# Alchemist.net
KiCad netlist of a schematic drawn in EAGLE
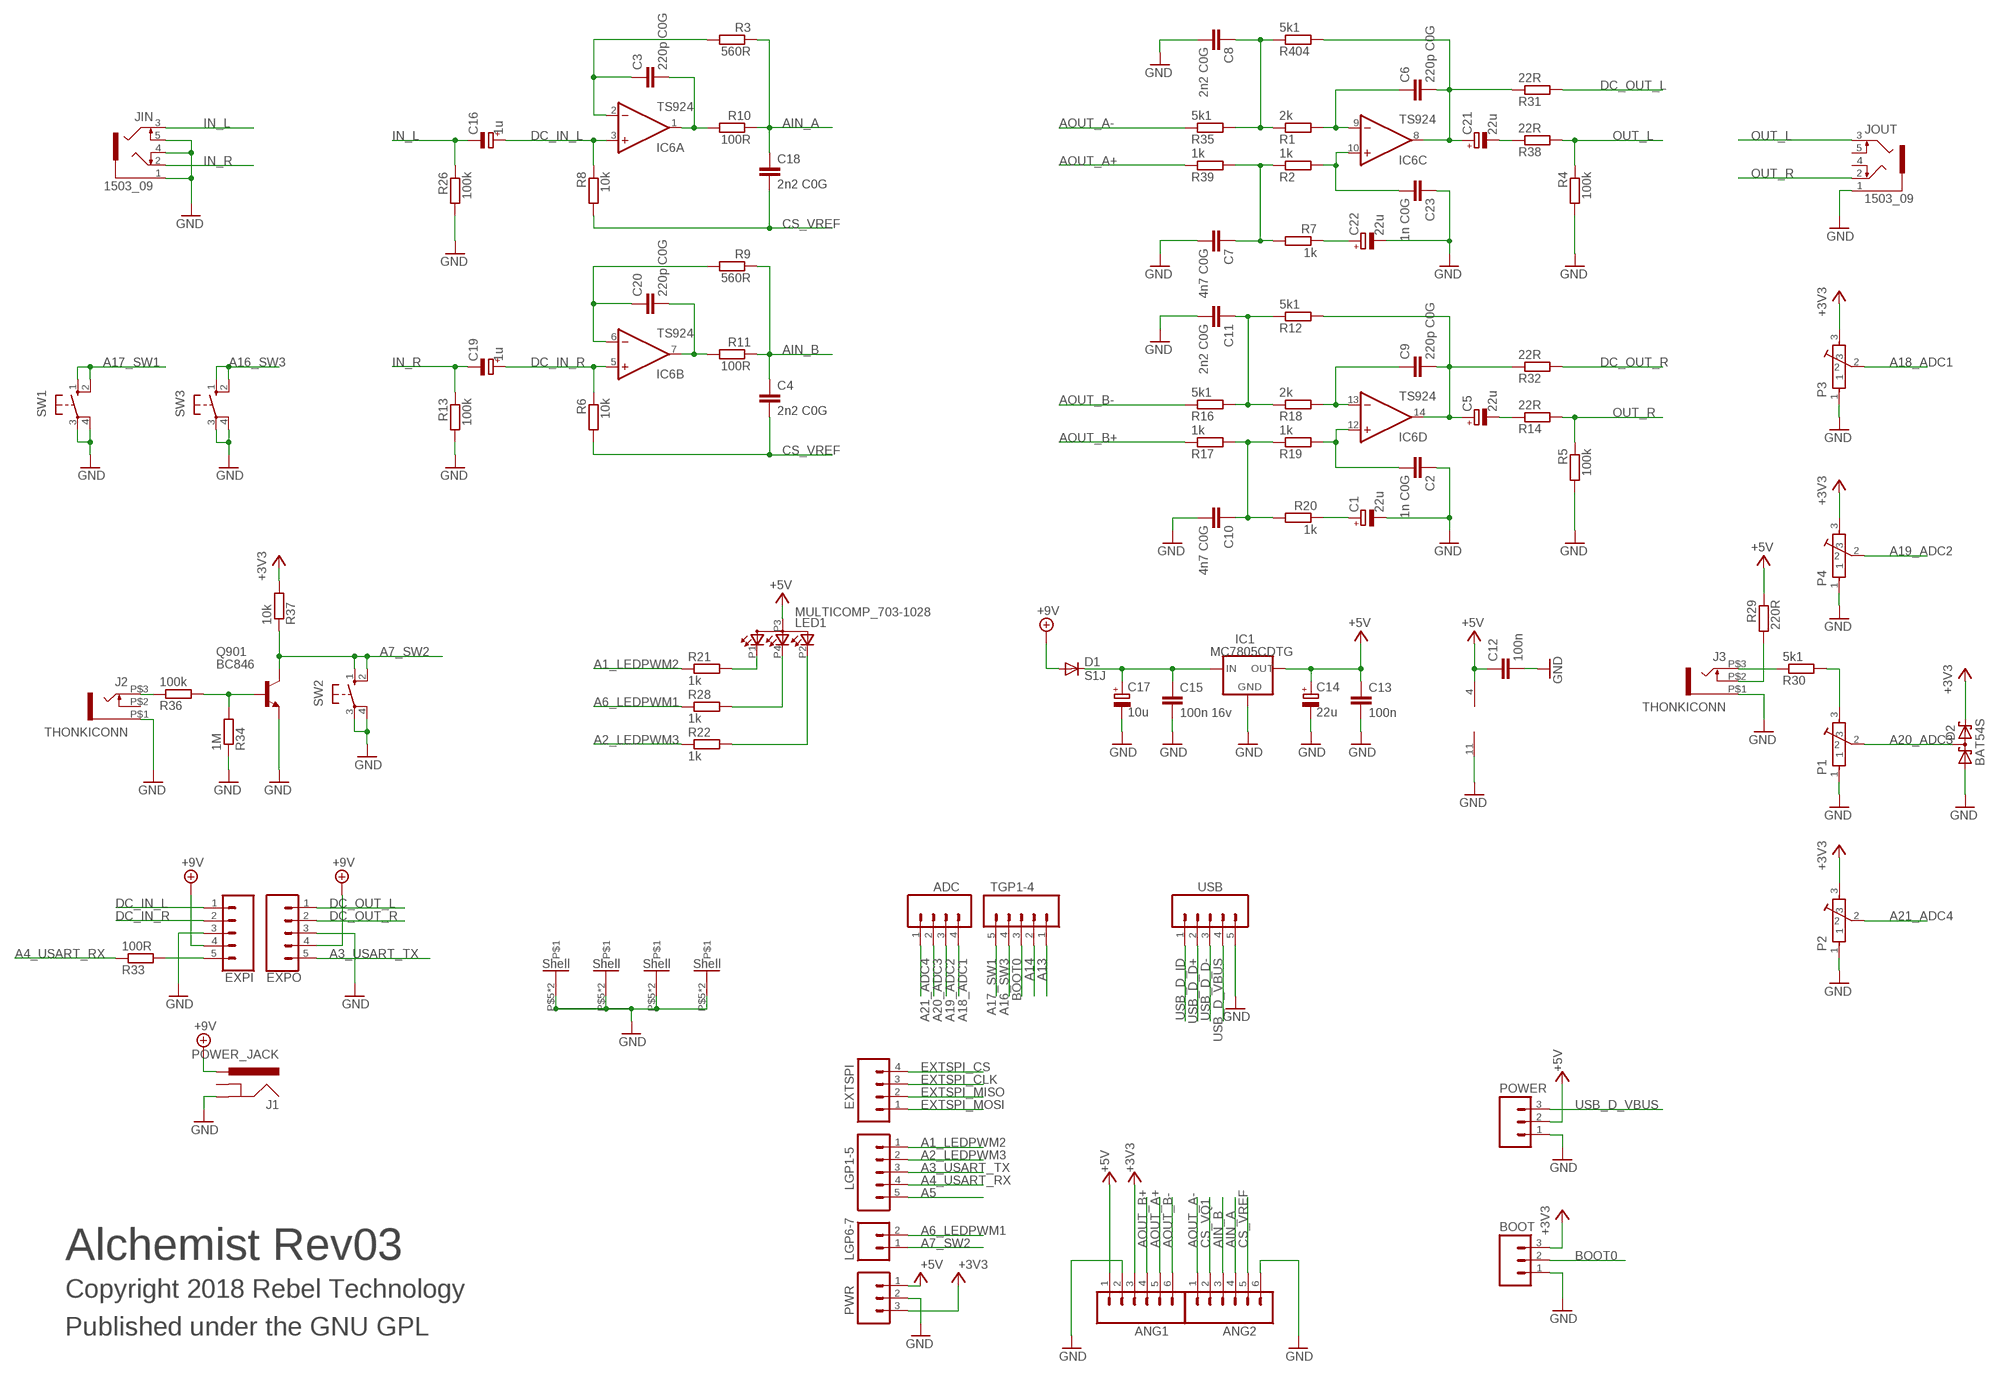
[diagram p0: schematic, sheet 1]

(export (version "E")
  (design (tool "Eeschema 10.0.6"))
  (components
    (comp (ref "ADC")
      (value "M04PTH")
      (footprint "eagle-import:1X04")
      (libsource (lib "eagle-import") (part "M04PTH"))
    )
    (comp (ref "ANG1")
      (value "M06SIP")
      (footprint "eagle-import:1X06")
      (libsource (lib "eagle-import") (part "M06SIP"))
    )
    (comp (ref "ANG2")
      (value "M06SIP")
      (footprint "eagle-import:1X06")
      (libsource (lib "eagle-import") (part "M06SIP"))
    )
    (comp (ref "BOOT")
      (value "M03PTH")
      (footprint "eagle-import:1X03")
      (libsource (lib "eagle-import") (part "M03PTH"))
    )
    (comp (ref "C1")
      (value "22u")
      (footprint "eagle-import:CPOL-5")
      (libsource (lib "eagle-import") (part "CPOL-EU153CLV-0505"))
    )
    (comp (ref "C2")
      (value "1n C0G")
      (footprint "eagle-import:C0603")
      (libsource (lib "eagle-import") (part "resistor_C-EUC0603"))
    )
    (comp (ref "C3")
      (value "220p C0G")
      (footprint "eagle-import:C0603")
      (libsource (lib "eagle-import") (part "resistor_C-EUC0603"))
    )
    (comp (ref "C4")
      (value "2n2 C0G")
      (footprint "eagle-import:C0603")
      (libsource (lib "eagle-import") (part "resistor_C-EUC0603"))
    )
    (comp (ref "C5")
      (value "22u")
      (footprint "eagle-import:CPOL-5")
      (libsource (lib "eagle-import") (part "CPOL-EU153CLV-0505"))
    )
    (comp (ref "C6")
      (value "220p C0G")
      (footprint "eagle-import:C0603")
      (libsource (lib "eagle-import") (part "resistor_C-EUC0603"))
    )
    (comp (ref "C7")
      (value "4n7 C0G")
      (footprint "eagle-import:C0603")
      (libsource (lib "eagle-import") (part "resistor_C-EUC0603"))
    )
    (comp (ref "C8")
      (value "2n2 C0G")
      (footprint "eagle-import:C0603")
      (libsource (lib "eagle-import") (part "resistor_C-EUC0603"))
    )
    (comp (ref "C9")
      (value "220p C0G")
      (footprint "eagle-import:C0603")
      (libsource (lib "eagle-import") (part "resistor_C-EUC0603"))
    )
    (comp (ref "C10")
      (value "4n7 C0G")
      (footprint "eagle-import:C0603")
      (libsource (lib "eagle-import") (part "resistor_C-EUC0603"))
    )
    (comp (ref "C11")
      (value "2n2 C0G")
      (footprint "eagle-import:C0603")
      (libsource (lib "eagle-import") (part "resistor_C-EUC0603"))
    )
    (comp (ref "C12")
      (value "100n")
      (footprint "eagle-import:C0603")
      (libsource (lib "eagle-import") (part "resistor_C-EUC0603"))
    )
    (comp (ref "C13")
      (value "100n")
      (footprint "eagle-import:C0603")
      (libsource (lib "eagle-import") (part "C-EUC0603"))
    )
    (comp (ref "C14")
      (value "22u")
      (footprint "eagle-import:CPOL-5")
      (libsource (lib "eagle-import") (part "CPOL-EU153CLV-0505"))
    )
    (comp (ref "C15")
      (value "100n 16v")
      (footprint "eagle-import:C0603")
      (libsource (lib "eagle-import") (part "C-EUC0603"))
    )
    (comp (ref "C16")
      (value "1u")
      (footprint "eagle-import:153CLV-0405")
      (libsource (lib "eagle-import") (part "CPOL-EU153CLV-0405"))
    )
    (comp (ref "C17")
      (value "10u")
      (footprint "eagle-import:153CLV-0405")
      (libsource (lib "eagle-import") (part "CPOL-EU153CLV-0405"))
    )
    (comp (ref "C18")
      (value "2n2 C0G")
      (footprint "eagle-import:C0603")
      (libsource (lib "eagle-import") (part "resistor_C-EUC0603"))
    )
    (comp (ref "C19")
      (value "1u")
      (footprint "eagle-import:153CLV-0405")
      (libsource (lib "eagle-import") (part "CPOL-EU153CLV-0405"))
    )
    (comp (ref "C20")
      (value "220p C0G")
      (footprint "eagle-import:C0603")
      (libsource (lib "eagle-import") (part "resistor_C-EUC0603"))
    )
    (comp (ref "C21")
      (value "22u")
      (footprint "eagle-import:CPOL-5")
      (libsource (lib "eagle-import") (part "CPOL-EU153CLV-0505"))
    )
    (comp (ref "C22")
      (value "22u")
      (footprint "eagle-import:CPOL-5")
      (libsource (lib "eagle-import") (part "CPOL-EU153CLV-0505"))
    )
    (comp (ref "C23")
      (value "1n C0G")
      (footprint "eagle-import:C0603")
      (libsource (lib "eagle-import") (part "resistor_C-EUC0603"))
    )
    (comp (ref "D1")
      (value "S1J")
      (footprint "eagle-import:SMA-DIODE")
      (libsource (lib "eagle-import") (part "DIODESMA"))
    )
    (comp (ref "D2")
      (value "BAT54S")
      (footprint "eagle-import:SOT23")
      (libsource (lib "eagle-import") (part "BAT54S"))
    )
    (comp (ref "EXPI")
      (value "CONN_05JST-VERT")
      (footprint "eagle-import:JST-5-PTH-VERT")
      (libsource (lib "eagle-import") (part "CONN_05JST-VERT"))
    )
    (comp (ref "EXPO")
      (value "CONN_05JST-VERT")
      (footprint "eagle-import:JST-5-PTH-VERT")
      (libsource (lib "eagle-import") (part "CONN_05JST-VERT"))
    )
    (comp (ref "EXTSPI")
      (value "M04PTH")
      (footprint "eagle-import:1X04")
      (libsource (lib "eagle-import") (part "M04PTH"))
    )
    (comp (ref "IC1")
      (value "MC7805CDTG")
      (footprint "eagle-import:DPACK")
      (libsource (lib "eagle-import") (part "MC78XX"))
    )
    (comp (ref "IC6")
      (value "TS924")
      (footprint "eagle-import:SO14")
      (libsource (lib "eagle-import") (part "LM324D"))
    )
    (comp (ref "J1")
      (value "POWER_JACK")
      (footprint "eagle-import:DC_JACK_SLOT")
      (libsource (lib "eagle-import") (part "POWER_JACK"))
    )
    (comp (ref "J2")
      (value "THONKICONN")
      (footprint "eagle-import:THONKICONN")
      (libsource (lib "eagle-import") (part "THONKICONN"))
    )
    (comp (ref "J3")
      (value "THONKICONN")
      (footprint "eagle-import:THONKICONN")
      (libsource (lib "eagle-import") (part "THONKICONN"))
    )
    (comp (ref "JIN")
      (value "1503_09")
      (footprint "eagle-import:1503_09")
      (libsource (lib "eagle-import") (part "1503_09"))
    )
    (comp (ref "JOUT")
      (value "1503_09")
      (footprint "eagle-import:1503_09")
      (libsource (lib "eagle-import") (part "1503_09"))
    )
    (comp (ref "LED1")
      (value "MULTICOMP_703-1028")
      (footprint "eagle-import:RGB-LED-703-1028")
      (libsource (lib "eagle-import") (part "MULTICOMP_703-1028"))
    )
    (comp (ref "LGP1-5")
      (value "M05PTH")
      (footprint "eagle-import:1X05")
      (libsource (lib "eagle-import") (part "M05PTH"))
    )
    (comp (ref "LGP6-7")
      (value "M02PTH")
      (footprint "eagle-import:1X02")
      (libsource (lib "eagle-import") (part "M02PTH"))
    )
    (comp (ref "P1")
      (value "POT-ALPS-RK09L1140")
      (footprint "eagle-import:POT-ALPS-RK09L1140")
      (libsource (lib "eagle-import") (part "POT-ALPS-RK09L1140"))
    )
    (comp (ref "P2")
      (value "POT-ALPS-RK09L1140")
      (footprint "eagle-import:POT-ALPS-RK09L1140")
      (libsource (lib "eagle-import") (part "POT-ALPS-RK09L1140"))
    )
    (comp (ref "P3")
      (value "POT-ALPS-RK09L1140")
      (footprint "eagle-import:POT-ALPS-RK09L1140")
      (libsource (lib "eagle-import") (part "POT-ALPS-RK09L1140"))
    )
    (comp (ref "P4")
      (value "POT-ALPS-RK09L1140")
      (footprint "eagle-import:POT-ALPS-RK09L1140")
      (libsource (lib "eagle-import") (part "POT-ALPS-RK09L1140"))
    )
    (comp (ref "POWER")
      (value "M03PTH")
      (footprint "eagle-import:1X03")
      (libsource (lib "eagle-import") (part "M03PTH"))
    )
    (comp (ref "PWR")
      (value "M03PTH")
      (footprint "eagle-import:1X03")
      (libsource (lib "eagle-import") (part "M03PTH"))
    )
    (comp (ref "Q901")
      (value "BC846")
      (footprint "eagle-import:SOT23")
      (libsource (lib "eagle-import") (part "BC846"))
    )
    (comp (ref "R1")
      (value "2k")
      (footprint "eagle-import:0603")
      (libsource (lib "eagle-import") (part "R-EU_0603"))
    )
    (comp (ref "R2")
      (value "1k")
      (footprint "eagle-import:0603")
      (libsource (lib "eagle-import") (part "R-EU_0603"))
    )
    (comp (ref "R3")
      (value "560R")
      (footprint "eagle-import:0603")
      (libsource (lib "eagle-import") (part "R-EU_0603"))
    )
    (comp (ref "R4")
      (value "100k")
      (footprint "eagle-import:0603")
      (libsource (lib "eagle-import") (part "R-EU_0603"))
    )
    (comp (ref "R5")
      (value "100k")
      (footprint "eagle-import:0603")
      (libsource (lib "eagle-import") (part "R-EU_0603"))
    )
    (comp (ref "R6")
      (value "10k")
      (footprint "eagle-import:0603")
      (libsource (lib "eagle-import") (part "R-EU_0603"))
    )
    (comp (ref "R7")
      (value "1k")
      (footprint "eagle-import:0603")
      (libsource (lib "eagle-import") (part "R-EU_0603"))
    )
    (comp (ref "R8")
      (value "10k")
      (footprint "eagle-import:0603")
      (libsource (lib "eagle-import") (part "R-EU_0603"))
    )
    (comp (ref "R9")
      (value "560R")
      (footprint "eagle-import:0603")
      (libsource (lib "eagle-import") (part "R-EU_0603"))
    )
    (comp (ref "R10")
      (value "100R")
      (footprint "eagle-import:0603")
      (libsource (lib "eagle-import") (part "R-EU_0603"))
    )
    (comp (ref "R11")
      (value "100R")
      (footprint "eagle-import:0603")
      (libsource (lib "eagle-import") (part "R-EU_0603"))
    )
    (comp (ref "R12")
      (value "5k1")
      (footprint "eagle-import:0603")
      (libsource (lib "eagle-import") (part "R-EU_0603"))
    )
    (comp (ref "R13")
      (value "100k")
      (footprint "eagle-import:0603")
      (libsource (lib "eagle-import") (part "R-EU_0603"))
    )
    (comp (ref "R14")
      (value "22R")
      (footprint "eagle-import:0603")
      (libsource (lib "eagle-import") (part "R-EU_0603"))
    )
    (comp (ref "R16")
      (value "5k1")
      (footprint "eagle-import:0603")
      (libsource (lib "eagle-import") (part "R-EU_0603"))
    )
    (comp (ref "R17")
      (value "1k")
      (footprint "eagle-import:0603")
      (libsource (lib "eagle-import") (part "R-EU_0603"))
    )
    (comp (ref "R18")
      (value "2k")
      (footprint "eagle-import:0603")
      (libsource (lib "eagle-import") (part "R-EU_0603"))
    )
    (comp (ref "R19")
      (value "1k")
      (footprint "eagle-import:0603")
      (libsource (lib "eagle-import") (part "R-EU_0603"))
    )
    (comp (ref "R20")
      (value "1k")
      (footprint "eagle-import:0603")
      (libsource (lib "eagle-import") (part "R-EU_0603"))
    )
    (comp (ref "R21")
      (value "1k")
      (footprint "eagle-import:0603")
      (libsource (lib "eagle-import") (part "R-EU_0603"))
    )
    (comp (ref "R22")
      (value "1k")
      (footprint "eagle-import:0603")
      (libsource (lib "eagle-import") (part "R-EU_0603"))
    )
    (comp (ref "R26")
      (value "100k")
      (footprint "eagle-import:0603")
      (libsource (lib "eagle-import") (part "R-EU_0603"))
    )
    (comp (ref "R28")
      (value "1k")
      (footprint "eagle-import:0603")
      (libsource (lib "eagle-import") (part "R-EU_0603"))
    )
    (comp (ref "R29")
      (value "220R")
      (footprint "eagle-import:0603")
      (libsource (lib "eagle-import") (part "R-EU_0603"))
    )
    (comp (ref "R30")
      (value "5k1")
      (footprint "eagle-import:0603")
      (libsource (lib "eagle-import") (part "R-EU_0603"))
    )
    (comp (ref "R31")
      (value "22R")
      (footprint "eagle-import:0603")
      (libsource (lib "eagle-import") (part "R-EU_0603"))
    )
    (comp (ref "R32")
      (value "22R")
      (footprint "eagle-import:0603")
      (libsource (lib "eagle-import") (part "R-EU_0603"))
    )
    (comp (ref "R33")
      (value "100R")
      (footprint "eagle-import:0603")
      (libsource (lib "eagle-import") (part "R-EU_0603"))
    )
    (comp (ref "R34")
      (value "1M")
      (footprint "eagle-import:0603")
      (libsource (lib "eagle-import") (part "R-EU_0603"))
    )
    (comp (ref "R35")
      (value "5k1")
      (footprint "eagle-import:0603")
      (libsource (lib "eagle-import") (part "R-EU_0603"))
    )
    (comp (ref "R36")
      (value "100k")
      (footprint "eagle-import:0603")
      (libsource (lib "eagle-import") (part "R-EU_0603"))
    )
    (comp (ref "R37")
      (value "10k")
      (footprint "eagle-import:0603")
      (libsource (lib "eagle-import") (part "R-EU_0603"))
    )
    (comp (ref "R38")
      (value "22R")
      (footprint "eagle-import:0603")
      (libsource (lib "eagle-import") (part "R-EU_0603"))
    )
    (comp (ref "R39")
      (value "1k")
      (footprint "eagle-import:0603")
      (libsource (lib "eagle-import") (part "R-EU_0603"))
    )
    (comp (ref "R404")
      (value "5k1")
      (footprint "eagle-import:0603")
      (libsource (lib "eagle-import") (part "R-EU_0603"))
    )
    (comp (ref "SW1")
      (value "10-XX")
      (footprint "eagle-import:B3F-10XX")
      (fields (field (name "MPN") "B3F-1000"))
      (libsource (lib "eagle-import") (part "10-XX"))
    )
    (comp (ref "SW2")
      (value "10-XX")
      (footprint "eagle-import:B3F-10XX")
      (fields (field (name "MPN") "B3F-1000"))
      (libsource (lib "eagle-import") (part "10-XX"))
    )
    (comp (ref "SW3")
      (value "10-XX")
      (footprint "eagle-import:B3F-10XX")
      (fields (field (name "MPN") "B3F-1000"))
      (libsource (lib "eagle-import") (part "10-XX"))
    )
    (comp (ref "TGP1-4")
      (value "M05PTH")
      (footprint "eagle-import:1X05")
      (libsource (lib "eagle-import") (part "M05PTH"))
    )
    (comp (ref "USB")
      (value "M05PTH")
      (footprint "eagle-import:1X05")
      (libsource (lib "eagle-import") (part "M05PTH"))
    )
  )
  (nets
    (net (code "1") (name "+3V3") (class "Default")
      (node (ref "ANG1") (pin "3") (pinfunction "3_3") (pintype "passive"))
      (node (ref "BOOT") (pin "3") (pinfunction "3_3") (pintype "passive"))
      (node (ref "D2") (pin "2") (pinfunction "C2_2") (pintype "passive"))
      (node (ref "P2") (pin "3") (pinfunction "3_3") (pintype "bidirectional"))
      (node (ref "P3") (pin "3") (pinfunction "3_3") (pintype "bidirectional"))
      (node (ref "P4") (pin "3") (pinfunction "3_3") (pintype "bidirectional"))
      (node (ref "PWR") (pin "3") (pinfunction "3_3") (pintype "passive"))
      (node (ref "R37") (pin "2") (pinfunction "2_2") (pintype "passive"))
    )
    (net (code "2") (name "+5V") (class "Default")
      (node (ref "ANG1") (pin "1") (pinfunction "1_1") (pintype "passive"))
      (node (ref "C12") (pin "1") (pinfunction "1_1") (pintype "passive"))
      (node (ref "C13") (pin "1") (pinfunction "1_1") (pintype "passive"))
      (node (ref "C14") (pin "+") (pinfunction "+_+") (pintype "passive"))
      (node (ref "IC1") (pin "3") (pinfunction "OUT_3") (pintype "passive"))
      (node (ref "IC6") (pin "4") (pinfunction "V+_4") (pintype "power_in"))
      (node (ref "LED1") (pin "P3") (pinfunction "A_P3") (pintype "passive"))
      (node (ref "POWER") (pin "2") (pinfunction "2_2") (pintype "passive"))
      (node (ref "PWR") (pin "1") (pinfunction "1_1") (pintype "passive"))
      (node (ref "R29") (pin "1") (pinfunction "1_1") (pintype "passive"))
    )
    (net (code "3") (name "+9V") (class "Default")
      (node (ref "D1") (pin "A") (pinfunction "A_A") (pintype "passive"))
      (node (ref "EXPI") (pin "4") (pinfunction "4_4") (pintype "passive"))
      (node (ref "EXPO") (pin "4") (pinfunction "4_4") (pintype "passive"))
      (node (ref "J1") (pin "PWR") (pinfunction "PWR_PWR") (pintype "bidirectional"))
    )
    (net (code "4") (name "/A1_LEDPWM2") (class "Default")
      (node (ref "LGP1-5") (pin "1") (pinfunction "1_1") (pintype "passive"))
      (node (ref "R21") (pin "1") (pinfunction "1_1") (pintype "passive"))
    )
    (net (code "5") (name "/A2_LEDPWM3") (class "Default")
      (node (ref "LGP1-5") (pin "2") (pinfunction "2_2") (pintype "passive"))
      (node (ref "R22") (pin "1") (pinfunction "1_1") (pintype "passive"))
    )
    (net (code "6") (name "/A3_USART_TX") (class "Default")
      (node (ref "EXPO") (pin "5") (pinfunction "5_5") (pintype "passive"))
      (node (ref "LGP1-5") (pin "3") (pinfunction "3_3") (pintype "passive"))
    )
    (net (code "7") (name "/A4_USART_RX") (class "Default")
      (node (ref "LGP1-5") (pin "4") (pinfunction "4_4") (pintype "passive"))
      (node (ref "R33") (pin "1") (pinfunction "1_1") (pintype "passive"))
    )
    (net (code "8") (name "/A5") (class "Default")
      (node (ref "LGP1-5") (pin "5") (pinfunction "5_5") (pintype "passive"))
    )
    (net (code "9") (name "/A6_LEDPWM1") (class "Default")
      (node (ref "LGP6-7") (pin "2") (pinfunction "2_2") (pintype "passive"))
      (node (ref "R28") (pin "1") (pinfunction "1_1") (pintype "passive"))
    )
    (net (code "10") (name "/A7_SW2") (class "Default")
      (node (ref "LGP6-7") (pin "1") (pinfunction "1_1") (pintype "passive"))
      (node (ref "Q901") (pin "3") (pinfunction "C_3") (pintype "passive"))
      (node (ref "R37") (pin "1") (pinfunction "1_1") (pintype "passive"))
      (node (ref "SW2") (pin "1") (pinfunction "S_1") (pintype "passive"))
      (node (ref "SW2") (pin "2") (pinfunction "S1_2") (pintype "passive"))
    )
    (net (code "11") (name "/A13") (class "Default")
      (node (ref "TGP1-4") (pin "1") (pinfunction "1_1") (pintype "passive"))
    )
    (net (code "12") (name "/A14") (class "Default")
      (node (ref "TGP1-4") (pin "2") (pinfunction "2_2") (pintype "passive"))
    )
    (net (code "13") (name "/A16_SW3") (class "Default")
      (node (ref "SW3") (pin "1") (pinfunction "S_1") (pintype "passive"))
      (node (ref "SW3") (pin "2") (pinfunction "S1_2") (pintype "passive"))
      (node (ref "TGP1-4") (pin "4") (pinfunction "4_4") (pintype "passive"))
    )
    (net (code "14") (name "/A17_SW1") (class "Default")
      (node (ref "SW1") (pin "1") (pinfunction "S_1") (pintype "passive"))
      (node (ref "SW1") (pin "2") (pinfunction "S1_2") (pintype "passive"))
      (node (ref "TGP1-4") (pin "5") (pinfunction "5_5") (pintype "passive"))
    )
    (net (code "15") (name "/A18_ADC1") (class "Default")
      (node (ref "ADC") (pin "4") (pinfunction "4_4") (pintype "passive"))
      (node (ref "P3") (pin "2") (pinfunction "2_2") (pintype "bidirectional"))
    )
    (net (code "16") (name "/A19_ADC2") (class "Default")
      (node (ref "ADC") (pin "3") (pinfunction "3_3") (pintype "passive"))
      (node (ref "P4") (pin "2") (pinfunction "2_2") (pintype "bidirectional"))
    )
    (net (code "17") (name "/A20_ADC3") (class "Default")
      (node (ref "ADC") (pin "2") (pinfunction "2_2") (pintype "passive"))
      (node (ref "D2") (pin "3") (pinfunction "C1A2_3") (pintype "passive"))
      (node (ref "P1") (pin "2") (pinfunction "2_2") (pintype "bidirectional"))
    )
    (net (code "18") (name "/A21_ADC4") (class "Default")
      (node (ref "ADC") (pin "1") (pinfunction "1_1") (pintype "passive"))
      (node (ref "P2") (pin "2") (pinfunction "2_2") (pintype "bidirectional"))
    )
    (net (code "19") (name "/AIN_A") (class "Default")
      (node (ref "ANG2") (pin "4") (pinfunction "4_4") (pintype "passive"))
      (node (ref "C18") (pin "1") (pinfunction "1_1") (pintype "passive"))
      (node (ref "R10") (pin "1") (pinfunction "1_1") (pintype "passive"))
      (node (ref "R3") (pin "1") (pinfunction "1_1") (pintype "passive"))
    )
    (net (code "20") (name "/AIN_B") (class "Default")
      (node (ref "ANG2") (pin "3") (pinfunction "3_3") (pintype "passive"))
      (node (ref "C4") (pin "1") (pinfunction "1_1") (pintype "passive"))
      (node (ref "R11") (pin "1") (pinfunction "1_1") (pintype "passive"))
      (node (ref "R9") (pin "1") (pinfunction "1_1") (pintype "passive"))
    )
    (net (code "21") (name "/AOUT_A+") (class "Default")
      (node (ref "ANG1") (pin "5") (pinfunction "5_5") (pintype "passive"))
      (node (ref "R39") (pin "1") (pinfunction "1_1") (pintype "passive"))
    )
    (net (code "22") (name "/AOUT_A-") (class "Default")
      (node (ref "ANG2") (pin "1") (pinfunction "1_1") (pintype "passive"))
      (node (ref "R35") (pin "1") (pinfunction "1_1") (pintype "passive"))
    )
    (net (code "23") (name "/AOUT_B+") (class "Default")
      (node (ref "ANG1") (pin "4") (pinfunction "4_4") (pintype "passive"))
      (node (ref "R17") (pin "1") (pinfunction "1_1") (pintype "passive"))
    )
    (net (code "24") (name "/AOUT_B-") (class "Default")
      (node (ref "ANG1") (pin "6") (pinfunction "6_6") (pintype "passive"))
      (node (ref "R16") (pin "1") (pinfunction "1_1") (pintype "passive"))
    )
    (net (code "25") (name "/BOOT0") (class "Default")
      (node (ref "BOOT") (pin "2") (pinfunction "2_2") (pintype "passive"))
      (node (ref "TGP1-4") (pin "3") (pinfunction "3_3") (pintype "passive"))
    )
    (net (code "26") (name "/CS_VQ1") (class "Default")
      (node (ref "ANG2") (pin "2") (pinfunction "2_2") (pintype "passive"))
    )
    (net (code "27") (name "/CS_VREF") (class "Default")
      (node (ref "ANG2") (pin "5") (pinfunction "5_5") (pintype "passive"))
      (node (ref "C18") (pin "2") (pinfunction "2_2") (pintype "passive"))
      (node (ref "C4") (pin "2") (pinfunction "2_2") (pintype "passive"))
      (node (ref "R6") (pin "2") (pinfunction "2_2") (pintype "passive"))
      (node (ref "R8") (pin "2") (pinfunction "2_2") (pintype "passive"))
    )
    (net (code "28") (name "/DC_IN_L") (class "Default")
      (node (ref "C16") (pin "+") (pinfunction "+_+") (pintype "passive"))
      (node (ref "EXPI") (pin "1") (pinfunction "1_1") (pintype "passive"))
      (node (ref "IC6") (pin "3") (pinfunction "+IN_3") (pintype "input"))
      (node (ref "R8") (pin "1") (pinfunction "1_1") (pintype "passive"))
    )
    (net (code "29") (name "/DC_IN_R") (class "Default")
      (node (ref "C19") (pin "+") (pinfunction "+_+") (pintype "passive"))
      (node (ref "EXPI") (pin "2") (pinfunction "2_2") (pintype "passive"))
      (node (ref "IC6") (pin "5") (pinfunction "+IN_5") (pintype "input"))
      (node (ref "R6") (pin "1") (pinfunction "1_1") (pintype "passive"))
    )
    (net (code "30") (name "/DC_OUT_L") (class "Default")
      (node (ref "EXPO") (pin "1") (pinfunction "1_1") (pintype "passive"))
      (node (ref "R31") (pin "2") (pinfunction "2_2") (pintype "passive"))
    )
    (net (code "31") (name "/DC_OUT_R") (class "Default")
      (node (ref "EXPO") (pin "2") (pinfunction "2_2") (pintype "passive"))
      (node (ref "R32") (pin "2") (pinfunction "2_2") (pintype "passive"))
    )
    (net (code "32") (name "/EXTSPI_CLK") (class "Default")
      (node (ref "EXTSPI") (pin "3") (pinfunction "3_3") (pintype "passive"))
    )
    (net (code "33") (name "/EXTSPI_CS") (class "Default")
      (node (ref "EXTSPI") (pin "4") (pinfunction "4_4") (pintype "passive"))
    )
    (net (code "34") (name "/EXTSPI_MISO") (class "Default")
      (node (ref "EXTSPI") (pin "2") (pinfunction "2_2") (pintype "passive"))
    )
    (net (code "35") (name "/EXTSPI_MOSI") (class "Default")
      (node (ref "EXTSPI") (pin "1") (pinfunction "1_1") (pintype "passive"))
    )
    (net (code "36") (name "/IN_L") (class "Default")
      (node (ref "C16") (pin "-") (pinfunction "-_-") (pintype "passive"))
      (node (ref "JIN") (pin "3") (pinfunction "3_3") (pintype "passive"))
      (node (ref "R26") (pin "1") (pinfunction "1_1") (pintype "passive"))
    )
    (net (code "37") (name "/IN_R") (class "Default")
      (node (ref "C19") (pin "-") (pinfunction "-_-") (pintype "passive"))
      (node (ref "JIN") (pin "2") (pinfunction "2_2") (pintype "passive"))
      (node (ref "R13") (pin "1") (pinfunction "1_1") (pintype "passive"))
    )
    (net (code "38") (name "/OUT_L") (class "Default")
      (node (ref "JOUT") (pin "3") (pinfunction "3_3") (pintype "passive"))
      (node (ref "R38") (pin "2") (pinfunction "2_2") (pintype "passive"))
      (node (ref "R4") (pin "1") (pinfunction "1_1") (pintype "passive"))
    )
    (net (code "39") (name "/OUT_R") (class "Default")
      (node (ref "JOUT") (pin "2") (pinfunction "2_2") (pintype "passive"))
      (node (ref "R14") (pin "2") (pinfunction "2_2") (pintype "passive"))
      (node (ref "R5") (pin "1") (pinfunction "1_1") (pintype "passive"))
    )
    (net (code "40") (name "/USB_D_D+") (class "Default")
      (node (ref "USB") (pin "2") (pinfunction "2_2") (pintype "passive"))
    )
    (net (code "41") (name "/USB_D_D-") (class "Default")
      (node (ref "USB") (pin "3") (pinfunction "3_3") (pintype "passive"))
    )
    (net (code "42") (name "/USB_D_ID") (class "Default")
      (node (ref "USB") (pin "1") (pinfunction "1_1") (pintype "passive"))
    )
    (net (code "43") (name "/USB_D_VBUS") (class "Default")
      (node (ref "POWER") (pin "3") (pinfunction "3_3") (pintype "passive"))
      (node (ref "USB") (pin "4") (pinfunction "4_4") (pintype "passive"))
    )
    (net (code "44") (name "GND") (class "Default")
      (node (ref "ANG1") (pin "2") (pinfunction "2_2") (pintype "passive"))
      (node (ref "ANG2") (pin "6") (pinfunction "6_6") (pintype "passive"))
      (node (ref "BOOT") (pin "1") (pinfunction "1_1") (pintype "passive"))
      (node (ref "C1") (pin "-") (pinfunction "-_-") (pintype "passive"))
      (node (ref "C10") (pin "2") (pinfunction "2_2") (pintype "passive"))
      (node (ref "C11") (pin "2") (pinfunction "2_2") (pintype "passive"))
      (node (ref "C12") (pin "2") (pinfunction "2_2") (pintype "passive"))
      (node (ref "C13") (pin "2") (pinfunction "2_2") (pintype "passive"))
      (node (ref "C14") (pin "-") (pinfunction "-_-") (pintype "passive"))
      (node (ref "C15") (pin "2") (pinfunction "2_2") (pintype "passive"))
      (node (ref "C17") (pin "-") (pinfunction "-_-") (pintype "passive"))
      (node (ref "C2") (pin "1") (pinfunction "1_1") (pintype "passive"))
      (node (ref "C22") (pin "-") (pinfunction "-_-") (pintype "passive"))
      (node (ref "C23") (pin "1") (pinfunction "1_1") (pintype "passive"))
      (node (ref "C7") (pin "2") (pinfunction "2_2") (pintype "passive"))
      (node (ref "C8") (pin "2") (pinfunction "2_2") (pintype "passive"))
      (node (ref "D2") (pin "1") (pinfunction "A1_1") (pintype "passive"))
      (node (ref "EXPI") (pin "3") (pinfunction "3_3") (pintype "passive"))
      (node (ref "EXPO") (pin "3") (pinfunction "3_3") (pintype "passive"))
      (node (ref "IC1") (pin "4") (pinfunction "GND_4") (pintype "input"))
      (node (ref "IC6") (pin "11") (pinfunction "V-_11") (pintype "power_in"))
      (node (ref "J1") (pin "GND") (pinfunction "GND_GND") (pintype "bidirectional"))
      (node (ref "J2") (pin "P$1") (pinfunction "5_P$1") (pintype "passive"))
      (node (ref "J3") (pin "P$1") (pinfunction "5_P$1") (pintype "passive"))
      (node (ref "JIN") (pin "1") (pinfunction "1_1") (pintype "passive"))
      (node (ref "JIN") (pin "4") (pinfunction "4_4") (pintype "passive"))
      (node (ref "JIN") (pin "5") (pinfunction "5_5") (pintype "passive"))
      (node (ref "JOUT") (pin "1") (pinfunction "1_1") (pintype "passive"))
      (node (ref "P1") (pin "1") (pinfunction "1_1") (pintype "bidirectional"))
      (node (ref "P1") (pin "P$5") (pinfunction "P$1_P$5") (pintype "bidirectional"))
      (node (ref "P1") (pin "P$6") (pinfunction "P$1_P$6") (pintype "bidirectional"))
      (node (ref "P2") (pin "1") (pinfunction "1_1") (pintype "bidirectional"))
      (node (ref "P2") (pin "P$5") (pinfunction "P$1_P$5") (pintype "bidirectional"))
      (node (ref "P2") (pin "P$6") (pinfunction "P$1_P$6") (pintype "bidirectional"))
      (node (ref "P3") (pin "1") (pinfunction "1_1") (pintype "bidirectional"))
      (node (ref "P3") (pin "P$5") (pinfunction "P$1_P$5") (pintype "bidirectional"))
      (node (ref "P3") (pin "P$6") (pinfunction "P$1_P$6") (pintype "bidirectional"))
      (node (ref "P4") (pin "1") (pinfunction "1_1") (pintype "bidirectional"))
      (node (ref "P4") (pin "P$5") (pinfunction "P$1_P$5") (pintype "bidirectional"))
      (node (ref "P4") (pin "P$6") (pinfunction "P$1_P$6") (pintype "bidirectional"))
      (node (ref "POWER") (pin "1") (pinfunction "1_1") (pintype "passive"))
      (node (ref "PWR") (pin "2") (pinfunction "2_2") (pintype "passive"))
      (node (ref "Q901") (pin "2") (pinfunction "E_2") (pintype "passive"))
      (node (ref "R13") (pin "2") (pinfunction "2_2") (pintype "passive"))
      (node (ref "R26") (pin "2") (pinfunction "2_2") (pintype "passive"))
      (node (ref "R34") (pin "1") (pinfunction "1_1") (pintype "passive"))
      (node (ref "R4") (pin "2") (pinfunction "2_2") (pintype "passive"))
      (node (ref "R5") (pin "2") (pinfunction "2_2") (pintype "passive"))
      (node (ref "SW1") (pin "3") (pinfunction "P_3") (pintype "passive"))
      (node (ref "SW1") (pin "4") (pinfunction "P1_4") (pintype "passive"))
      (node (ref "SW2") (pin "3") (pinfunction "P_3") (pintype "passive"))
      (node (ref "SW2") (pin "4") (pinfunction "P1_4") (pintype "passive"))
      (node (ref "SW3") (pin "3") (pinfunction "P_3") (pintype "passive"))
      (node (ref "SW3") (pin "4") (pinfunction "P1_4") (pintype "passive"))
      (node (ref "USB") (pin "5") (pinfunction "5_5") (pintype "passive"))
    )
    (net (code "45") (name "Net-(C1-Pad+)") (class "Default")
      (node (ref "C1") (pin "+") (pinfunction "+_+") (pintype "passive"))
      (node (ref "R20") (pin "1") (pinfunction "1_1") (pintype "passive"))
    )
    (net (code "46") (name "Net-(C5-Pad-)") (class "Default")
      (node (ref "C5") (pin "-") (pinfunction "-_-") (pintype "passive"))
      (node (ref "R14") (pin "1") (pinfunction "1_1") (pintype "passive"))
    )
    (net (code "47") (name "Net-(C7-Pad1)") (class "Default")
      (node (ref "C7") (pin "1") (pinfunction "1_1") (pintype "passive"))
      (node (ref "R2") (pin "1") (pinfunction "1_1") (pintype "passive"))
      (node (ref "R39") (pin "2") (pinfunction "2_2") (pintype "passive"))
      (node (ref "R7") (pin "2") (pinfunction "2_2") (pintype "passive"))
    )
    (net (code "48") (name "Net-(C8-Pad1)") (class "Default")
      (node (ref "C8") (pin "1") (pinfunction "1_1") (pintype "passive"))
      (node (ref "R1") (pin "1") (pinfunction "1_1") (pintype "passive"))
      (node (ref "R35") (pin "2") (pinfunction "2_2") (pintype "passive"))
      (node (ref "R404") (pin "1") (pinfunction "1_1") (pintype "passive"))
    )
    (net (code "49") (name "Net-(C10-Pad1)") (class "Default")
      (node (ref "C10") (pin "1") (pinfunction "1_1") (pintype "passive"))
      (node (ref "R17") (pin "2") (pinfunction "2_2") (pintype "passive"))
      (node (ref "R19") (pin "1") (pinfunction "1_1") (pintype "passive"))
      (node (ref "R20") (pin "2") (pinfunction "2_2") (pintype "passive"))
    )
    (net (code "50") (name "Net-(C11-Pad1)") (class "Default")
      (node (ref "C11") (pin "1") (pinfunction "1_1") (pintype "passive"))
      (node (ref "R12") (pin "1") (pinfunction "1_1") (pintype "passive"))
      (node (ref "R16") (pin "2") (pinfunction "2_2") (pintype "passive"))
      (node (ref "R18") (pin "1") (pinfunction "1_1") (pintype "passive"))
    )
    (net (code "51") (name "Net-(C21-Pad-)") (class "Default")
      (node (ref "C21") (pin "-") (pinfunction "-_-") (pintype "passive"))
      (node (ref "R38") (pin "1") (pinfunction "1_1") (pintype "passive"))
    )
    (net (code "52") (name "Net-(C22-Pad+)") (class "Default")
      (node (ref "C22") (pin "+") (pinfunction "+_+") (pintype "passive"))
      (node (ref "R7") (pin "1") (pinfunction "1_1") (pintype "passive"))
    )
    (net (code "53") (name "Net-(EXPI-Pad5)") (class "Default")
      (node (ref "EXPI") (pin "5") (pinfunction "5_5") (pintype "passive"))
      (node (ref "R33") (pin "2") (pinfunction "2_2") (pintype "passive"))
    )
    (net (code "54") (name "Net-(IC1-IN)") (class "Default")
      (node (ref "C15") (pin "1") (pinfunction "1_1") (pintype "passive"))
      (node (ref "C17") (pin "+") (pinfunction "+_+") (pintype "passive"))
      (node (ref "D1") (pin "C") (pinfunction "C_C") (pintype "passive"))
      (node (ref "IC1") (pin "1") (pinfunction "IN_1") (pintype "input"))
    )
    (net (code "55") (name "Net-(IC6A--IN)") (class "Default")
      (node (ref "C3") (pin "1") (pinfunction "1_1") (pintype "passive"))
      (node (ref "IC6") (pin "2") (pinfunction "-IN_2") (pintype "input"))
      (node (ref "R3") (pin "2") (pinfunction "2_2") (pintype "passive"))
    )
    (net (code "56") (name "Net-(IC6A-OUT)") (class "Default")
      (node (ref "C3") (pin "2") (pinfunction "2_2") (pintype "passive"))
      (node (ref "IC6") (pin "1") (pinfunction "OUT_1") (pintype "output"))
      (node (ref "R10") (pin "2") (pinfunction "2_2") (pintype "passive"))
    )
    (net (code "57") (name "Net-(IC6B--IN)") (class "Default")
      (node (ref "C20") (pin "1") (pinfunction "1_1") (pintype "passive"))
      (node (ref "IC6") (pin "6") (pinfunction "-IN_6") (pintype "input"))
      (node (ref "R9") (pin "2") (pinfunction "2_2") (pintype "passive"))
    )
    (net (code "58") (name "Net-(IC6B-OUT)") (class "Default")
      (node (ref "C20") (pin "2") (pinfunction "2_2") (pintype "passive"))
      (node (ref "IC6") (pin "7") (pinfunction "OUT_7") (pintype "output"))
      (node (ref "R11") (pin "2") (pinfunction "2_2") (pintype "passive"))
    )
    (net (code "59") (name "Net-(IC6C-+IN)") (class "Default")
      (node (ref "C23") (pin "2") (pinfunction "2_2") (pintype "passive"))
      (node (ref "IC6") (pin "10") (pinfunction "+IN_10") (pintype "input"))
      (node (ref "R2") (pin "2") (pinfunction "2_2") (pintype "passive"))
    )
    (net (code "60") (name "Net-(IC6C--IN)") (class "Default")
      (node (ref "C6") (pin "1") (pinfunction "1_1") (pintype "passive"))
      (node (ref "IC6") (pin "9") (pinfunction "-IN_9") (pintype "input"))
      (node (ref "R1") (pin "2") (pinfunction "2_2") (pintype "passive"))
    )
    (net (code "61") (name "Net-(IC6C-OUT)") (class "Default")
      (node (ref "C21") (pin "+") (pinfunction "+_+") (pintype "passive"))
      (node (ref "C6") (pin "2") (pinfunction "2_2") (pintype "passive"))
      (node (ref "IC6") (pin "8") (pinfunction "OUT_8") (pintype "output"))
      (node (ref "R31") (pin "1") (pinfunction "1_1") (pintype "passive"))
      (node (ref "R404") (pin "2") (pinfunction "2_2") (pintype "passive"))
    )
    (net (code "62") (name "Net-(IC6D-+IN)") (class "Default")
      (node (ref "C2") (pin "2") (pinfunction "2_2") (pintype "passive"))
      (node (ref "IC6") (pin "12") (pinfunction "+IN_12") (pintype "input"))
      (node (ref "R19") (pin "2") (pinfunction "2_2") (pintype "passive"))
    )
    (net (code "63") (name "Net-(IC6D--IN)") (class "Default")
      (node (ref "C9") (pin "1") (pinfunction "1_1") (pintype "passive"))
      (node (ref "IC6") (pin "13") (pinfunction "-IN_13") (pintype "input"))
      (node (ref "R18") (pin "2") (pinfunction "2_2") (pintype "passive"))
    )
    (net (code "64") (name "Net-(IC6D-OUT)") (class "Default")
      (node (ref "C5") (pin "+") (pinfunction "+_+") (pintype "passive"))
      (node (ref "C9") (pin "2") (pinfunction "2_2") (pintype "passive"))
      (node (ref "IC6") (pin "14") (pinfunction "OUT_14") (pintype "output"))
      (node (ref "R12") (pin "2") (pinfunction "2_2") (pintype "passive"))
      (node (ref "R32") (pin "1") (pinfunction "1_1") (pintype "passive"))
    )
    (net (code "65") (name "Net-(J2-3)") (class "Default")
      (node (ref "J2") (pin "P$3") (pinfunction "3_P$3") (pintype "passive"))
      (node (ref "R36") (pin "1") (pinfunction "1_1") (pintype "passive"))
    )
    (net (code "66") (name "Net-(J3-3)") (class "Default")
      (node (ref "J3") (pin "P$3") (pinfunction "3_P$3") (pintype "passive"))
      (node (ref "R30") (pin "1") (pinfunction "1_1") (pintype "passive"))
    )
    (net (code "67") (name "Net-(J3-4)") (class "Default")
      (node (ref "J3") (pin "P$2") (pinfunction "4_P$2") (pintype "passive"))
      (node (ref "R29") (pin "2") (pinfunction "2_2") (pintype "passive"))
    )
    (net (code "68") (name "Net-(LED1-CBLUE)") (class "Default")
      (node (ref "LED1") (pin "P4") (pinfunction "CBLUE_P4") (pintype "passive"))
      (node (ref "R28") (pin "2") (pinfunction "2_2") (pintype "passive"))
    )
    (net (code "69") (name "Net-(LED1-CGREEN)") (class "Default")
      (node (ref "LED1") (pin "P2") (pinfunction "CGREEN_P2") (pintype "passive"))
      (node (ref "R22") (pin "2") (pinfunction "2_2") (pintype "passive"))
    )
    (net (code "70") (name "Net-(LED1-CRED)") (class "Default")
      (node (ref "LED1") (pin "P1") (pinfunction "CRED_P1") (pintype "passive"))
      (node (ref "R21") (pin "2") (pinfunction "2_2") (pintype "passive"))
    )
    (net (code "71") (name "Net-(P1-Pad3)") (class "Default")
      (node (ref "P1") (pin "3") (pinfunction "3_3") (pintype "bidirectional"))
      (node (ref "R30") (pin "2") (pinfunction "2_2") (pintype "passive"))
    )
    (net (code "72") (name "Net-(Q901-B)") (class "Default")
      (node (ref "Q901") (pin "1") (pinfunction "B_1") (pintype "passive"))
      (node (ref "R34") (pin "2") (pinfunction "2_2") (pintype "passive"))
      (node (ref "R36") (pin "2") (pinfunction "2_2") (pintype "passive"))
    )
    (net (code "73") (name "unconnected-(J1-PadGNDBREAK)") (class "Default")
      (node (ref "J1") (pin "GNDBREAK") (pinfunction "GNDBREAK_GNDBREAK") (pintype "bidirectional"))
    )
    (net (code "74") (name "unconnected-(J2-4-PadP$2)") (class "Default")
      (node (ref "J2") (pin "P$2") (pinfunction "4_P$2") (pintype "passive"))
    )
    (net (code "75") (name "unconnected-(JOUT-Pad4)") (class "Default")
      (node (ref "JOUT") (pin "4") (pinfunction "4_4") (pintype "passive"))
    )
    (net (code "76") (name "unconnected-(JOUT-Pad5)") (class "Default")
      (node (ref "JOUT") (pin "5") (pinfunction "5_5") (pintype "passive"))
    )
  )
)
